# PRO1.net
KiCad netlist of a schematic drawn in Altium Designer
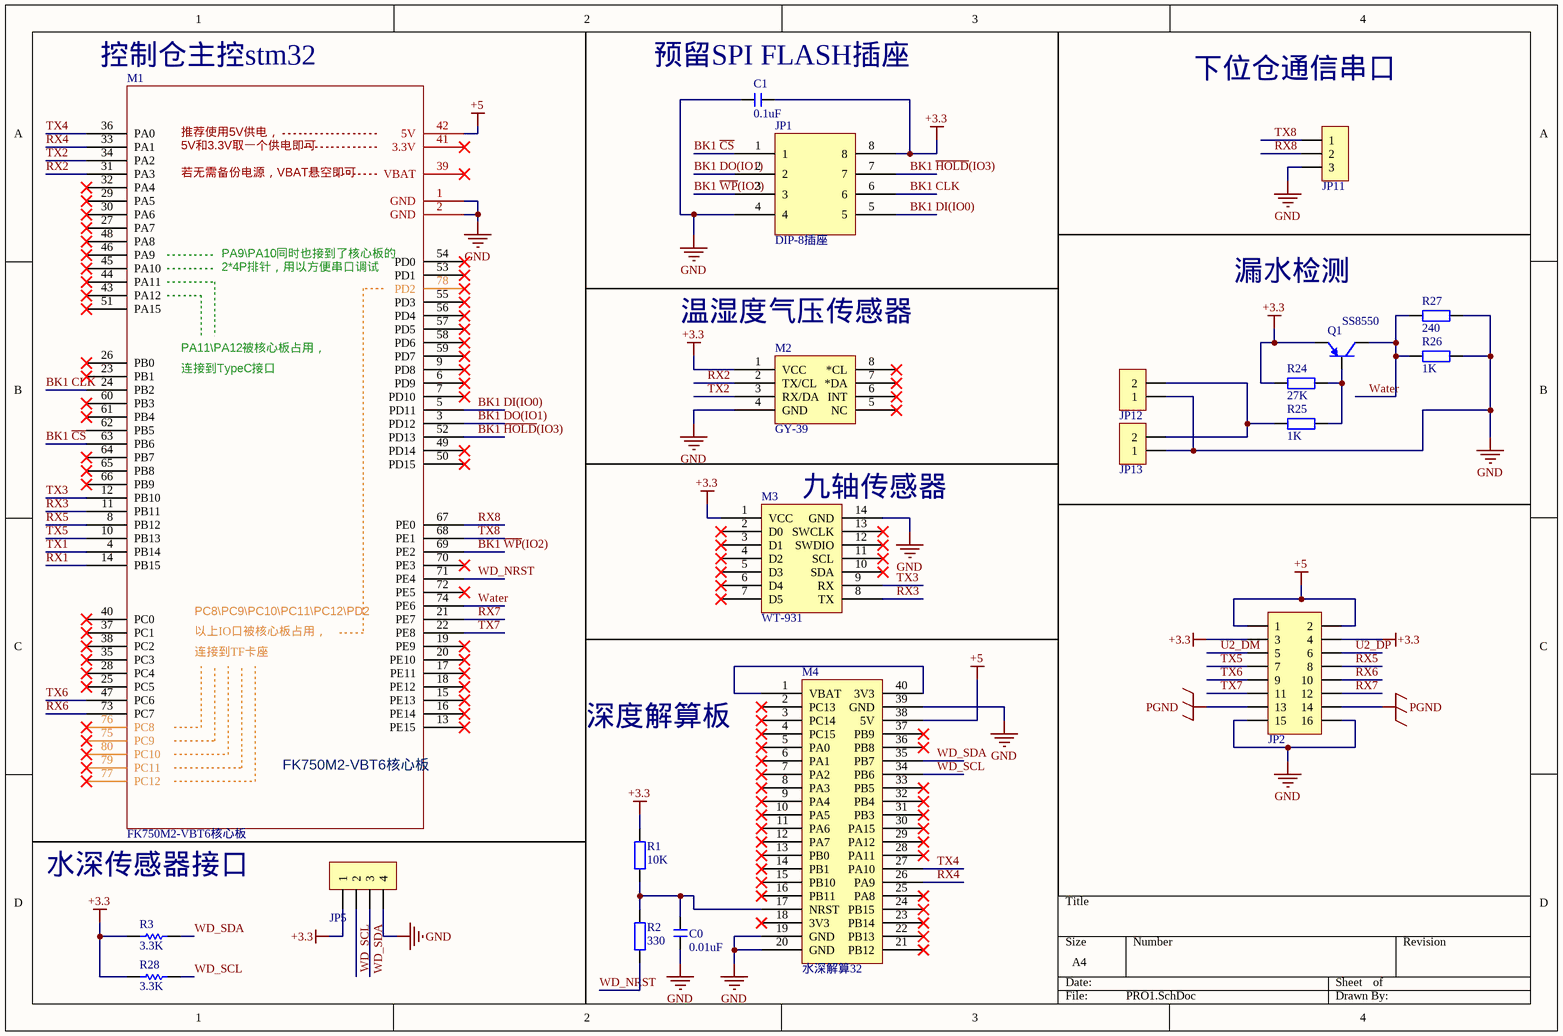
[diagram p0: PRO1.SchDoc]

(export (version "E")
  (design (tool "Eeschema 10.0.6"))
  (components
    (comp (ref "C0")
      (value "0.01uF")
      (footprint "C 0603_M")
      (description "无极性贴片电容")
      (fields (field (name "版权归属") "源创客"))
      (libsource (lib "3.1   - 电阻-电容-电感") (part "C"))
    )
    (comp (ref "C1")
      (value "0.1uF")
      (footprint "C 0603_M")
      (description "无极性贴片电容")
      (fields (field (name "版权归属") "源创客"))
      (libsource (lib "3.1   - 电阻-电容-电感") (part "C"))
    )
    (comp (ref "JP1")
      (value "DIP-8插座")
      (footprint "DIP-8座")
      (libsource (lib "FK750M2模块-原理图库") (part "DIP-8插座"))
    )
    (comp (ref "JP2")
      (value "Header 8X2")
      (footprint "IDC2.54-LI-2x8P")
      (description "8*2P接插件")
      (fields (field (name "版权归属") "源创客"))
      (libsource (lib "4.5   - 接插件-脚距2.54") (part "Header 8X2"))
    )
    (comp (ref "JP5")
      (value "HDR-1X4")
      (footprint "MX 1.25-LS-4P")
      (description "4P接插件")
      (fields (field (name "版权归属") "源创客"))
      (libsource (lib "4.2   - 接插件-脚距1.25") (part "Header 4"))
    )
    (comp (ref "JP11")
      (value "HDR-1X3")
      (footprint "PH2.0-LS-3P")
      (description "3P接插件")
      (fields (field (name "版权归属") "源创客"))
      (libsource (lib "4.4   - 接插件-脚距2.0") (part "Header 3"))
    )
    (comp (ref "JP12")
      (value "HDR-1X2")
      (footprint "GH1.25")
      (description "2P接插件")
      (fields (field (name "版权归属") "源创客"))
      (libsource (lib "4.2   - 接插件-脚距1.25") (part "Header 2"))
    )
    (comp (ref "JP13")
      (value "HDR-1X2")
      (footprint "GH1.25")
      (description "2P接插件")
      (fields (field (name "版权归属") "源创客"))
      (libsource (lib "4.2   - 接插件-脚距1.25") (part "Header 2"))
    )
    (comp (ref "M1")
      (value "FK750M2-VBT6核心板")
      (footprint "FK750M2-VBT6(精简版)")
      (libsource (lib "FK750M2模块-原理图库") (part "FK750M2-VBT6"))
    )
    (comp (ref "M2")
      (value "GY-39")
      (footprint "GY-39")
      (description "气压温湿度光强传感器")
      (libsource (lib "sensor") (part "GY-39"))
    )
    (comp (ref "M3")
      (value "WT-931")
      (footprint "WT-931")
      (description "WT-931姿态角度传感器")
      (libsource (lib "sensor") (part "WT-931"))
    )
    (comp (ref "M4")
      (value "水深解算32")
      (footprint "Deep_32")
      (description "水深传感器解算用的stm32模块")
      (libsource (lib "sensor") (part "Deep_32"))
    )
    (comp (ref "Q1")
      (value "SS8550")
      (footprint "SOT23-3M")
      (description "高频放大-PNP型")
      (fields (field (name "版权归属") "源创客"))
      (libsource (lib "6.2   - 三极管") (part "8550-SMD"))
    )
    (comp (ref "R1")
      (value "10K")
      (footprint "R 0603_M")
      (description "贴片电阻")
      (fields (field (name "版权归属") "源创客"))
      (libsource (lib "3.1   - 电阻-电容-电感") (part "R"))
    )
    (comp (ref "R2")
      (value "330")
      (footprint "R 0805_L")
      (description "贴片电阻")
      (fields (field (name "版权归属") "源创客"))
      (libsource (lib "3.1   - 电阻-电容-电感") (part "R"))
    )
    (comp (ref "R3") (value "3.3K") (footprint "0603R") (libsource (lib "电阻") (part "RES")))
    (comp (ref "R24")
      (value "27K")
      (footprint "R 0603_M")
      (description "贴片电阻")
      (fields (field (name "版权归属") "源创客"))
      (libsource (lib "3.1   - 电阻-电容-电感") (part "R"))
    )
    (comp (ref "R25")
      (value "1K")
      (footprint "R 0603_M")
      (description "贴片电阻")
      (fields (field (name "版权归属") "源创客"))
      (libsource (lib "3.1   - 电阻-电容-电感") (part "R"))
    )
    (comp (ref "R26")
      (value "1K")
      (footprint "R 0603_M")
      (description "贴片电阻")
      (fields (field (name "版权归属") "源创客"))
      (libsource (lib "3.1   - 电阻-电容-电感") (part "R"))
    )
    (comp (ref "R27")
      (value "240")
      (footprint "R 0603_M")
      (description "贴片电阻")
      (fields (field (name "版权归属") "源创客"))
      (libsource (lib "3.1   - 电阻-电容-电感") (part "R"))
    )
    (comp (ref "R28") (value "3.3K") (footprint "0603R") (libsource (lib "电阻") (part "RES")))
  )
  (nets
    (net (code "1") (name "+3.3") (class "Default")
      (node (ref "C1") (pin "2") (pinfunction "2_2") (pintype "passive"))
      (node (ref "JP1") (pin "8") (pinfunction "8_8") (pintype "passive"))
      (node (ref "JP2") (pin "3") (pinfunction "3_3") (pintype "passive"))
      (node (ref "JP2") (pin "4") (pinfunction "4_4") (pintype "passive"))
      (node (ref "JP5") (pin "1") (pinfunction "1_1") (pintype "passive"))
      (node (ref "M2") (pin "1") (pinfunction "VCC_1") (pintype "passive"))
      (node (ref "M3") (pin "1") (pinfunction "VCC_1") (pintype "passive"))
      (node (ref "Q1") (pin "2") (pinfunction "E_2") (pintype "passive"))
      (node (ref "R1") (pin "2") (pinfunction "2_2") (pintype "passive"))
      (node (ref "R24") (pin "1") (pinfunction "1_1") (pintype "passive"))
      (node (ref "R28") (pin "1") (pinfunction "1_1") (pintype "passive"))
      (node (ref "R3") (pin "1") (pinfunction "1_1") (pintype "passive"))
    )
    (net (code "2") (name "+5") (class "Default")
      (node (ref "JP2") (pin "1") (pinfunction "1_1") (pintype "passive"))
      (node (ref "JP2") (pin "2") (pinfunction "2_2") (pintype "passive"))
      (node (ref "M1") (pin "42") (pinfunction "5V_42") (pintype "passive"))
      (node (ref "M4") (pin "38") (pinfunction "5V_38") (pintype "passive"))
    )
    (net (code "3") (name "/BK1 CLK") (class "Default")
      (node (ref "JP1") (pin "6") (pinfunction "6_6") (pintype "passive"))
      (node (ref "M1") (pin "24") (pinfunction "PB2_24") (pintype "passive"))
    )
    (net (code "4") (name "/BK1 DI(IO0)") (class "Default")
      (node (ref "JP1") (pin "5") (pinfunction "5_5") (pintype "passive"))
      (node (ref "M1") (pin "5") (pinfunction "PD11_5") (pintype "passive"))
    )
    (net (code "5") (name "/BK1 DO(IO1)") (class "Default")
      (node (ref "JP1") (pin "2") (pinfunction "2_2") (pintype "passive"))
      (node (ref "M1") (pin "3") (pinfunction "PD12_3") (pintype "passive"))
    )
    (net (code "6") (name "/BK1 ~{CS}") (class "Default")
      (node (ref "JP1") (pin "1") (pinfunction "1_1") (pintype "passive"))
      (node (ref "M1") (pin "63") (pinfunction "PB6_63") (pintype "passive"))
    )
    (net (code "7") (name "/BK1 ~{HOLD}(IO3)") (class "Default")
      (node (ref "JP1") (pin "7") (pinfunction "7_7") (pintype "passive"))
      (node (ref "M1") (pin "52") (pinfunction "PD13_52") (pintype "passive"))
    )
    (net (code "8") (name "/BK1 ~{WP}(IO2)") (class "Default")
      (node (ref "JP1") (pin "3") (pinfunction "3_3") (pintype "passive"))
      (node (ref "M1") (pin "69") (pinfunction "PE2_69") (pintype "passive"))
    )
    (net (code "9") (name "/RX1") (class "Default")
      (node (ref "M1") (pin "14") (pinfunction "PB15_14") (pintype "passive"))
    )
    (net (code "10") (name "/RX2") (class "Default")
      (node (ref "M1") (pin "31") (pinfunction "PA3_31") (pintype "passive"))
      (node (ref "M2") (pin "2") (pinfunction "TX/CL_2") (pintype "passive"))
    )
    (net (code "11") (name "/RX3") (class "Default")
      (node (ref "M1") (pin "11") (pinfunction "PB11_11") (pintype "passive"))
      (node (ref "M3") (pin "8") (pinfunction "TX_8") (pintype "passive"))
    )
    (net (code "12") (name "/RX4") (class "Default")
      (node (ref "M1") (pin "33") (pinfunction "PA1_33") (pintype "passive"))
      (node (ref "M4") (pin "26") (pinfunction "PA9_26") (pintype "passive"))
    )
    (net (code "13") (name "/RX5") (class "Default")
      (node (ref "JP2") (pin "8") (pinfunction "8_8") (pintype "passive"))
      (node (ref "M1") (pin "8") (pinfunction "PB12_8") (pintype "passive"))
    )
    (net (code "14") (name "/RX6") (class "Default")
      (node (ref "JP2") (pin "10") (pinfunction "10_10") (pintype "passive"))
      (node (ref "M1") (pin "73") (pinfunction "PC7_73") (pintype "passive"))
    )
    (net (code "15") (name "/RX7") (class "Default")
      (node (ref "JP2") (pin "12") (pinfunction "12_12") (pintype "passive"))
      (node (ref "M1") (pin "21") (pinfunction "PE7_21") (pintype "passive"))
    )
    (net (code "16") (name "/RX8") (class "Default")
      (node (ref "JP11") (pin "2") (pinfunction "2_2") (pintype "passive"))
      (node (ref "M1") (pin "67") (pinfunction "PE0_67") (pintype "passive"))
    )
    (net (code "17") (name "/TX1") (class "Default")
      (node (ref "M1") (pin "4") (pinfunction "PB14_4") (pintype "passive"))
    )
    (net (code "18") (name "/TX2") (class "Default")
      (node (ref "M1") (pin "34") (pinfunction "PA2_34") (pintype "passive"))
      (node (ref "M2") (pin "3") (pinfunction "RX/DA_3") (pintype "passive"))
    )
    (net (code "19") (name "/TX3") (class "Default")
      (node (ref "M1") (pin "12") (pinfunction "PB10_12") (pintype "passive"))
      (node (ref "M3") (pin "9") (pinfunction "RX_9") (pintype "passive"))
    )
    (net (code "20") (name "/TX4") (class "Default")
      (node (ref "M1") (pin "36") (pinfunction "PA0_36") (pintype "passive"))
      (node (ref "M4") (pin "27") (pinfunction "PA10_27") (pintype "passive"))
    )
    (net (code "21") (name "/TX5") (class "Default")
      (node (ref "JP2") (pin "7") (pinfunction "7_7") (pintype "passive"))
      (node (ref "M1") (pin "10") (pinfunction "PB13_10") (pintype "passive"))
    )
    (net (code "22") (name "/TX6") (class "Default")
      (node (ref "JP2") (pin "9") (pinfunction "9_9") (pintype "passive"))
      (node (ref "M1") (pin "47") (pinfunction "PC6_47") (pintype "passive"))
    )
    (net (code "23") (name "/TX7") (class "Default")
      (node (ref "JP2") (pin "11") (pinfunction "11_11") (pintype "passive"))
      (node (ref "M1") (pin "22") (pinfunction "PE8_22") (pintype "passive"))
    )
    (net (code "24") (name "/TX8") (class "Default")
      (node (ref "JP11") (pin "1") (pinfunction "1_1") (pintype "passive"))
      (node (ref "M1") (pin "68") (pinfunction "PE1_68") (pintype "passive"))
    )
    (net (code "25") (name "/U2_DM") (class "Default")
      (node (ref "JP2") (pin "5") (pinfunction "5_5") (pintype "passive"))
    )
    (net (code "26") (name "/U2_DP") (class "Default")
      (node (ref "JP2") (pin "6") (pinfunction "6_6") (pintype "passive"))
    )
    (net (code "27") (name "/WD_NRST") (class "Default")
      (node (ref "M1") (pin "71") (pinfunction "PE4_71") (pintype "passive"))
      (node (ref "R2") (pin "1") (pinfunction "1_1") (pintype "passive"))
    )
    (net (code "28") (name "/WD_SCL") (class "Default")
      (node (ref "JP5") (pin "2") (pinfunction "2_2") (pintype "passive"))
      (node (ref "M4") (pin "34") (pinfunction "PB6_34") (pintype "passive"))
      (node (ref "R28") (pin "2") (pinfunction "2_2") (pintype "passive"))
    )
    (net (code "29") (name "/WD_SDA") (class "Default")
      (node (ref "JP5") (pin "3") (pinfunction "3_3") (pintype "passive"))
      (node (ref "M4") (pin "35") (pinfunction "PB7_35") (pintype "passive"))
      (node (ref "R3") (pin "2") (pinfunction "2_2") (pintype "passive"))
    )
    (net (code "30") (name "/Water") (class "Default")
      (node (ref "M1") (pin "74") (pinfunction "PE6_74") (pintype "passive"))
      (node (ref "Q1") (pin "3") (pinfunction "C_3") (pintype "passive"))
      (node (ref "R26") (pin "2") (pinfunction "2_2") (pintype "passive"))
      (node (ref "R27") (pin "1") (pinfunction "1_1") (pintype "passive"))
    )
    (net (code "31") (name "GND") (class "Default")
      (node (ref "C0") (pin "1") (pinfunction "1_1") (pintype "passive"))
      (node (ref "C1") (pin "1") (pinfunction "1_1") (pintype "passive"))
      (node (ref "JP1") (pin "4") (pinfunction "4_4") (pintype "passive"))
      (node (ref "JP11") (pin "3") (pinfunction "3_3") (pintype "passive"))
      (node (ref "JP12") (pin "1") (pinfunction "1_1") (pintype "passive"))
      (node (ref "JP13") (pin "1") (pinfunction "1_1") (pintype "passive"))
      (node (ref "JP2") (pin "15") (pinfunction "15_15") (pintype "passive"))
      (node (ref "JP2") (pin "16") (pinfunction "16_16") (pintype "passive"))
      (node (ref "JP5") (pin "4") (pinfunction "4_4") (pintype "passive"))
      (node (ref "M1") (pin "1") (pinfunction "GND_1") (pintype "passive"))
      (node (ref "M1") (pin "2") (pinfunction "GND_2") (pintype "passive"))
      (node (ref "M2") (pin "4") (pinfunction "GND_4") (pintype "passive"))
      (node (ref "M3") (pin "14") (pinfunction "GND_14") (pintype "passive"))
      (node (ref "M4") (pin "19") (pinfunction "GND_19") (pintype "passive"))
      (node (ref "M4") (pin "20") (pinfunction "GND_20") (pintype "passive"))
      (node (ref "M4") (pin "39") (pinfunction "GND_39") (pintype "passive"))
      (node (ref "R26") (pin "1") (pinfunction "1_1") (pintype "passive"))
      (node (ref "R27") (pin "2") (pinfunction "2_2") (pintype "passive"))
    )
    (net (code "32") (name "Net-(JP12-Pad2)") (class "Default")
      (node (ref "JP12") (pin "2") (pinfunction "2_2") (pintype "passive"))
      (node (ref "JP13") (pin "2") (pinfunction "2_2") (pintype "passive"))
      (node (ref "R25") (pin "2") (pinfunction "2_2") (pintype "passive"))
    )
    (net (code "33") (name "Net-(M4-NRST)") (class "Default")
      (node (ref "C0") (pin "2") (pinfunction "2_2") (pintype "passive"))
      (node (ref "M4") (pin "17") (pinfunction "NRST_17") (pintype "passive"))
      (node (ref "R1") (pin "1") (pinfunction "1_1") (pintype "passive"))
      (node (ref "R2") (pin "2") (pinfunction "2_2") (pintype "passive"))
    )
    (net (code "34") (name "Net-(M4-VBAT)") (class "Default")
      (node (ref "M4") (pin "1") (pinfunction "VBAT_1") (pintype "passive"))
      (node (ref "M4") (pin "40") (pinfunction "3V3_40") (pintype "passive"))
    )
    (net (code "35") (name "Net-(Q1-B)") (class "Default")
      (node (ref "Q1") (pin "1") (pinfunction "B_1") (pintype "passive"))
      (node (ref "R24") (pin "2") (pinfunction "2_2") (pintype "passive"))
      (node (ref "R25") (pin "1") (pinfunction "1_1") (pintype "passive"))
    )
    (net (code "36") (name "PGND") (class "Default")
      (node (ref "JP2") (pin "13") (pinfunction "13_13") (pintype "passive"))
      (node (ref "JP2") (pin "14") (pinfunction "14_14") (pintype "passive"))
    )
    (net (code "37") (name "unconnected-(M1-3.3V-Pad41)") (class "Default")
      (node (ref "M1") (pin "41") (pinfunction "3.3V_41") (pintype "passive+no_connect"))
    )
    (net (code "38") (name "unconnected-(M1-PA4-Pad32)") (class "Default")
      (node (ref "M1") (pin "32") (pinfunction "PA4_32") (pintype "passive+no_connect"))
    )
    (net (code "39") (name "unconnected-(M1-PA5-Pad29)") (class "Default")
      (node (ref "M1") (pin "29") (pinfunction "PA5_29") (pintype "passive+no_connect"))
    )
    (net (code "40") (name "unconnected-(M1-PA6-Pad30)") (class "Default")
      (node (ref "M1") (pin "30") (pinfunction "PA6_30") (pintype "passive+no_connect"))
    )
    (net (code "41") (name "unconnected-(M1-PA7-Pad27)") (class "Default")
      (node (ref "M1") (pin "27") (pinfunction "PA7_27") (pintype "passive+no_connect"))
    )
    (net (code "42") (name "unconnected-(M1-PA8-Pad48)") (class "Default")
      (node (ref "M1") (pin "48") (pinfunction "PA8_48") (pintype "passive+no_connect"))
    )
    (net (code "43") (name "unconnected-(M1-PA9-Pad46)") (class "Default")
      (node (ref "M1") (pin "46") (pinfunction "PA9_46") (pintype "passive+no_connect"))
    )
    (net (code "44") (name "unconnected-(M1-PA10-Pad45)") (class "Default")
      (node (ref "M1") (pin "45") (pinfunction "PA10_45") (pintype "passive+no_connect"))
    )
    (net (code "45") (name "unconnected-(M1-PA11-Pad44)") (class "Default")
      (node (ref "M1") (pin "44") (pinfunction "PA11_44") (pintype "passive+no_connect"))
    )
    (net (code "46") (name "unconnected-(M1-PA12-Pad43)") (class "Default")
      (node (ref "M1") (pin "43") (pinfunction "PA12_43") (pintype "passive+no_connect"))
    )
    (net (code "47") (name "unconnected-(M1-PA15-Pad51)") (class "Default")
      (node (ref "M1") (pin "51") (pinfunction "PA15_51") (pintype "passive+no_connect"))
    )
    (net (code "48") (name "unconnected-(M1-PB0-Pad26)") (class "Default")
      (node (ref "M1") (pin "26") (pinfunction "PB0_26") (pintype "passive+no_connect"))
    )
    (net (code "49") (name "unconnected-(M1-PB1-Pad23)") (class "Default")
      (node (ref "M1") (pin "23") (pinfunction "PB1_23") (pintype "passive+no_connect"))
    )
    (net (code "50") (name "unconnected-(M1-PB3-Pad60)") (class "Default")
      (node (ref "M1") (pin "60") (pinfunction "PB3_60") (pintype "passive+no_connect"))
    )
    (net (code "51") (name "unconnected-(M1-PB4-Pad61)") (class "Default")
      (node (ref "M1") (pin "61") (pinfunction "PB4_61") (pintype "passive+no_connect"))
    )
    (net (code "52") (name "unconnected-(M1-PB5-Pad62)") (class "Default")
      (node (ref "M1") (pin "62") (pinfunction "PB5_62") (pintype "passive"))
    )
    (net (code "53") (name "unconnected-(M1-PB7-Pad64)") (class "Default")
      (node (ref "M1") (pin "64") (pinfunction "PB7_64") (pintype "passive+no_connect"))
    )
    (net (code "54") (name "unconnected-(M1-PB8-Pad65)") (class "Default")
      (node (ref "M1") (pin "65") (pinfunction "PB8_65") (pintype "passive+no_connect"))
    )
    (net (code "55") (name "unconnected-(M1-PB9-Pad66)") (class "Default")
      (node (ref "M1") (pin "66") (pinfunction "PB9_66") (pintype "passive+no_connect"))
    )
    (net (code "56") (name "unconnected-(M1-PC0-Pad40)") (class "Default")
      (node (ref "M1") (pin "40") (pinfunction "PC0_40") (pintype "passive+no_connect"))
    )
    (net (code "57") (name "unconnected-(M1-PC1-Pad37)") (class "Default")
      (node (ref "M1") (pin "37") (pinfunction "PC1_37") (pintype "passive+no_connect"))
    )
    (net (code "58") (name "unconnected-(M1-PC2-Pad38)") (class "Default")
      (node (ref "M1") (pin "38") (pinfunction "PC2_38") (pintype "passive+no_connect"))
    )
    (net (code "59") (name "unconnected-(M1-PC3-Pad35)") (class "Default")
      (node (ref "M1") (pin "35") (pinfunction "PC3_35") (pintype "passive+no_connect"))
    )
    (net (code "60") (name "unconnected-(M1-PC4-Pad28)") (class "Default")
      (node (ref "M1") (pin "28") (pinfunction "PC4_28") (pintype "passive+no_connect"))
    )
    (net (code "61") (name "unconnected-(M1-PC5-Pad25)") (class "Default")
      (node (ref "M1") (pin "25") (pinfunction "PC5_25") (pintype "passive+no_connect"))
    )
    (net (code "62") (name "unconnected-(M1-PC8-Pad76)") (class "Default")
      (node (ref "M1") (pin "76") (pinfunction "PC8_76") (pintype "passive+no_connect"))
    )
    (net (code "63") (name "unconnected-(M1-PC9-Pad75)") (class "Default")
      (node (ref "M1") (pin "75") (pinfunction "PC9_75") (pintype "passive+no_connect"))
    )
    (net (code "64") (name "unconnected-(M1-PC10-Pad80)") (class "Default")
      (node (ref "M1") (pin "80") (pinfunction "PC10_80") (pintype "passive+no_connect"))
    )
    (net (code "65") (name "unconnected-(M1-PC11-Pad79)") (class "Default")
      (node (ref "M1") (pin "79") (pinfunction "PC11_79") (pintype "passive+no_connect"))
    )
    (net (code "66") (name "unconnected-(M1-PC12-Pad77)") (class "Default")
      (node (ref "M1") (pin "77") (pinfunction "PC12_77") (pintype "passive+no_connect"))
    )
    (net (code "67") (name "unconnected-(M1-PD0-Pad54)") (class "Default")
      (node (ref "M1") (pin "54") (pinfunction "PD0_54") (pintype "passive+no_connect"))
    )
    (net (code "68") (name "unconnected-(M1-PD1-Pad53)") (class "Default")
      (node (ref "M1") (pin "53") (pinfunction "PD1_53") (pintype "passive+no_connect"))
    )
    (net (code "69") (name "unconnected-(M1-PD2-Pad78)") (class "Default")
      (node (ref "M1") (pin "78") (pinfunction "PD2_78") (pintype "passive+no_connect"))
    )
    (net (code "70") (name "unconnected-(M1-PD3-Pad55)") (class "Default")
      (node (ref "M1") (pin "55") (pinfunction "PD3_55") (pintype "passive+no_connect"))
    )
    (net (code "71") (name "unconnected-(M1-PD4-Pad56)") (class "Default")
      (node (ref "M1") (pin "56") (pinfunction "PD4_56") (pintype "passive+no_connect"))
    )
    (net (code "72") (name "unconnected-(M1-PD5-Pad57)") (class "Default")
      (node (ref "M1") (pin "57") (pinfunction "PD5_57") (pintype "passive+no_connect"))
    )
    (net (code "73") (name "unconnected-(M1-PD6-Pad58)") (class "Default")
      (node (ref "M1") (pin "58") (pinfunction "PD6_58") (pintype "passive+no_connect"))
    )
    (net (code "74") (name "unconnected-(M1-PD7-Pad59)") (class "Default")
      (node (ref "M1") (pin "59") (pinfunction "PD7_59") (pintype "passive+no_connect"))
    )
    (net (code "75") (name "unconnected-(M1-PD8-Pad9)") (class "Default")
      (node (ref "M1") (pin "9") (pinfunction "PD8_9") (pintype "passive+no_connect"))
    )
    (net (code "76") (name "unconnected-(M1-PD9-Pad6)") (class "Default")
      (node (ref "M1") (pin "6") (pinfunction "PD9_6") (pintype "passive+no_connect"))
    )
    (net (code "77") (name "unconnected-(M1-PD10-Pad7)") (class "Default")
      (node (ref "M1") (pin "7") (pinfunction "PD10_7") (pintype "passive+no_connect"))
    )
    (net (code "78") (name "unconnected-(M1-PD14-Pad49)") (class "Default")
      (node (ref "M1") (pin "49") (pinfunction "PD14_49") (pintype "passive+no_connect"))
    )
    (net (code "79") (name "unconnected-(M1-PD15-Pad50)") (class "Default")
      (node (ref "M1") (pin "50") (pinfunction "PD15_50") (pintype "passive+no_connect"))
    )
    (net (code "80") (name "unconnected-(M1-PE3-Pad70)") (class "Default")
      (node (ref "M1") (pin "70") (pinfunction "PE3_70") (pintype "passive+no_connect"))
    )
    (net (code "81") (name "unconnected-(M1-PE5-Pad72)") (class "Default")
      (node (ref "M1") (pin "72") (pinfunction "PE5_72") (pintype "passive+no_connect"))
    )
    (net (code "82") (name "unconnected-(M1-PE9-Pad19)") (class "Default")
      (node (ref "M1") (pin "19") (pinfunction "PE9_19") (pintype "passive+no_connect"))
    )
    (net (code "83") (name "unconnected-(M1-PE10-Pad20)") (class "Default")
      (node (ref "M1") (pin "20") (pinfunction "PE10_20") (pintype "passive+no_connect"))
    )
    (net (code "84") (name "unconnected-(M1-PE11-Pad17)") (class "Default")
      (node (ref "M1") (pin "17") (pinfunction "PE11_17") (pintype "passive+no_connect"))
    )
    (net (code "85") (name "unconnected-(M1-PE12-Pad18)") (class "Default")
      (node (ref "M1") (pin "18") (pinfunction "PE12_18") (pintype "passive+no_connect"))
    )
    (net (code "86") (name "unconnected-(M1-PE13-Pad15)") (class "Default")
      (node (ref "M1") (pin "15") (pinfunction "PE13_15") (pintype "passive+no_connect"))
    )
    (net (code "87") (name "unconnected-(M1-PE14-Pad16)") (class "Default")
      (node (ref "M1") (pin "16") (pinfunction "PE14_16") (pintype "passive+no_connect"))
    )
    (net (code "88") (name "unconnected-(M1-PE15-Pad13)") (class "Default")
      (node (ref "M1") (pin "13") (pinfunction "PE15_13") (pintype "passive+no_connect"))
    )
    (net (code "89") (name "unconnected-(M1-VBAT-Pad39)") (class "Default")
      (node (ref "M1") (pin "39") (pinfunction "VBAT_39") (pintype "passive+no_connect"))
    )
    (net (code "90") (name "unconnected-(M2-*CL-Pad8)") (class "Default")
      (node (ref "M2") (pin "8") (pinfunction "*CL_8") (pintype "passive+no_connect"))
    )
    (net (code "91") (name "unconnected-(M2-*DA-Pad7)") (class "Default")
      (node (ref "M2") (pin "7") (pinfunction "*DA_7") (pintype "passive+no_connect"))
    )
    (net (code "92") (name "unconnected-(M2-INT-Pad6)") (class "Default")
      (node (ref "M2") (pin "6") (pinfunction "INT_6") (pintype "passive+no_connect"))
    )
    (net (code "93") (name "unconnected-(M2-NC-Pad5)") (class "Default")
      (node (ref "M2") (pin "5") (pinfunction "NC_5") (pintype "passive+no_connect"))
    )
    (net (code "94") (name "unconnected-(M3-D0-Pad2)") (class "Default")
      (node (ref "M3") (pin "2") (pinfunction "D0_2") (pintype "passive+no_connect"))
    )
    (net (code "95") (name "unconnected-(M3-D1-Pad3)") (class "Default")
      (node (ref "M3") (pin "3") (pinfunction "D1_3") (pintype "passive+no_connect"))
    )
    (net (code "96") (name "unconnected-(M3-D2-Pad4)") (class "Default")
      (node (ref "M3") (pin "4") (pinfunction "D2_4") (pintype "passive+no_connect"))
    )
    (net (code "97") (name "unconnected-(M3-D3-Pad5)") (class "Default")
      (node (ref "M3") (pin "5") (pinfunction "D3_5") (pintype "passive+no_connect"))
    )
    (net (code "98") (name "unconnected-(M3-D4-Pad6)") (class "Default")
      (node (ref "M3") (pin "6") (pinfunction "D4_6") (pintype "passive+no_connect"))
    )
    (net (code "99") (name "unconnected-(M3-D5-Pad7)") (class "Default")
      (node (ref "M3") (pin "7") (pinfunction "D5_7") (pintype "passive+no_connect"))
    )
    (net (code "100") (name "unconnected-(M3-SCL-Pad11)") (class "Default")
      (node (ref "M3") (pin "11") (pinfunction "SCL_11") (pintype "passive+no_connect"))
    )
    (net (code "101") (name "unconnected-(M3-SDA-Pad10)") (class "Default")
      (node (ref "M3") (pin "10") (pinfunction "SDA_10") (pintype "passive+no_connect"))
    )
    (net (code "102") (name "unconnected-(M3-SWCLK-Pad13)") (class "Default")
      (node (ref "M3") (pin "13") (pinfunction "SWCLK_13") (pintype "passive+no_connect"))
    )
    (net (code "103") (name "unconnected-(M3-SWDIO-Pad12)") (class "Default")
      (node (ref "M3") (pin "12") (pinfunction "SWDIO_12") (pintype "passive+no_connect"))
    )
    (net (code "104") (name "unconnected-(M4-3V3-Pad18)") (class "Default")
      (node (ref "M4") (pin "18") (pinfunction "3V3_18") (pintype "passive+no_connect"))
    )
    (net (code "105") (name "unconnected-(M4-PA0-Pad5)") (class "Default")
      (node (ref "M4") (pin "5") (pinfunction "PA0_5") (pintype "passive+no_connect"))
    )
    (net (code "106") (name "unconnected-(M4-PA1-Pad6)") (class "Default")
      (node (ref "M4") (pin "6") (pinfunction "PA1_6") (pintype "passive+no_connect"))
    )
    (net (code "107") (name "unconnected-(M4-PA2-Pad7)") (class "Default")
      (node (ref "M4") (pin "7") (pinfunction "PA2_7") (pintype "passive+no_connect"))
    )
    (net (code "108") (name "unconnected-(M4-PA3-Pad8)") (class "Default")
      (node (ref "M4") (pin "8") (pinfunction "PA3_8") (pintype "passive+no_connect"))
    )
    (net (code "109") (name "unconnected-(M4-PA4-Pad9)") (class "Default")
      (node (ref "M4") (pin "9") (pinfunction "PA4_9") (pintype "passive+no_connect"))
    )
    (net (code "110") (name "unconnected-(M4-PA5-Pad10)") (class "Default")
      (node (ref "M4") (pin "10") (pinfunction "PA5_10") (pintype "passive+no_connect"))
    )
    (net (code "111") (name "unconnected-(M4-PA6-Pad11)") (class "Default")
      (node (ref "M4") (pin "11") (pinfunction "PA6_11") (pintype "passive+no_connect"))
    )
    (net (code "112") (name "unconnected-(M4-PA7-Pad12)") (class "Default")
      (node (ref "M4") (pin "12") (pinfunction "PA7_12") (pintype "passive+no_connect"))
    )
    (net (code "113") (name "unconnected-(M4-PA8-Pad25)") (class "Default")
      (node (ref "M4") (pin "25") (pinfunction "PA8_25") (pintype "passive+no_connect"))
    )
    (net (code "114") (name "unconnected-(M4-PA11-Pad28)") (class "Default")
      (node (ref "M4") (pin "28") (pinfunction "PA11_28") (pintype "passive+no_connect"))
    )
    (net (code "115") (name "unconnected-(M4-PA12-Pad29)") (class "Default")
      (node (ref "M4") (pin "29") (pinfunction "PA12_29") (pintype "passive+no_connect"))
    )
    (net (code "116") (name "unconnected-(M4-PA15-Pad30)") (class "Default")
      (node (ref "M4") (pin "30") (pinfunction "PA15_30") (pintype "passive+no_connect"))
    )
    (net (code "117") (name "unconnected-(M4-PB0-Pad13)") (class "Default")
      (node (ref "M4") (pin "13") (pinfunction "PB0_13") (pintype "passive+no_connect"))
    )
    (net (code "118") (name "unconnected-(M4-PB1-Pad14)") (class "Default")
      (node (ref "M4") (pin "14") (pinfunction "PB1_14") (pintype "passive+no_connect"))
    )
    (net (code "119") (name "unconnected-(M4-PB3-Pad31)") (class "Default")
      (node (ref "M4") (pin "31") (pinfunction "PB3_31") (pintype "passive+no_connect"))
    )
    (net (code "120") (name "unconnected-(M4-PB4-Pad32)") (class "Default")
      (node (ref "M4") (pin "32") (pinfunction "PB4_32") (pintype "passive+no_connect"))
    )
    (net (code "121") (name "unconnected-(M4-PB5-Pad33)") (class "Default")
      (node (ref "M4") (pin "33") (pinfunction "PB5_33") (pintype "passive+no_connect"))
    )
    (net (code "122") (name "unconnected-(M4-PB8-Pad36)") (class "Default")
      (node (ref "M4") (pin "36") (pinfunction "PB8_36") (pintype "passive+no_connect"))
    )
    (net (code "123") (name "unconnected-(M4-PB9-Pad37)") (class "Default")
      (node (ref "M4") (pin "37") (pinfunction "PB9_37") (pintype "passive+no_connect"))
    )
    (net (code "124") (name "unconnected-(M4-PB10-Pad15)") (class "Default")
      (node (ref "M4") (pin "15") (pinfunction "PB10_15") (pintype "passive+no_connect"))
    )
    (net (code "125") (name "unconnected-(M4-PB11-Pad16)") (class "Default")
      (node (ref "M4") (pin "16") (pinfunction "PB11_16") (pintype "passive+no_connect"))
    )
    (net (code "126") (name "unconnected-(M4-PB12-Pad21)") (class "Default")
      (node (ref "M4") (pin "21") (pinfunction "PB12_21") (pintype "passive+no_connect"))
    )
    (net (code "127") (name "unconnected-(M4-PB13-Pad22)") (class "Default")
      (node (ref "M4") (pin "22") (pinfunction "PB13_22") (pintype "passive+no_connect"))
    )
    (net (code "128") (name "unconnected-(M4-PB14-Pad23)") (class "Default")
      (node (ref "M4") (pin "23") (pinfunction "PB14_23") (pintype "passive+no_connect"))
    )
    (net (code "129") (name "unconnected-(M4-PB15-Pad24)") (class "Default")
      (node (ref "M4") (pin "24") (pinfunction "PB15_24") (pintype "passive+no_connect"))
    )
    (net (code "130") (name "unconnected-(M4-PC13-Pad2)") (class "Default")
      (node (ref "M4") (pin "2") (pinfunction "PC13_2") (pintype "passive+no_connect"))
    )
    (net (code "131") (name "unconnected-(M4-PC14-Pad3)") (class "Default")
      (node (ref "M4") (pin "3") (pinfunction "PC14_3") (pintype "passive+no_connect"))
    )
    (net (code "132") (name "unconnected-(M4-PC15-Pad4)") (class "Default")
      (node (ref "M4") (pin "4") (pinfunction "PC15_4") (pintype "passive+no_connect"))
    )
  )
)
